# Sheet6.net
KiCad netlist of a schematic drawn in Altium Designer
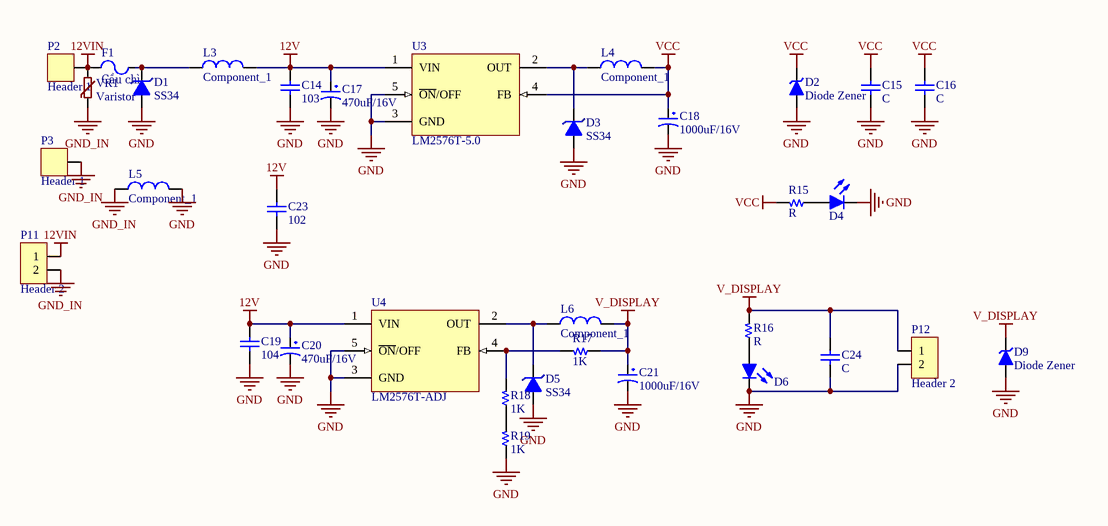
[diagram p0: Sheet6.SchDoc]

(export (version "E")
  (design (tool "Eeschema 10.0.6"))
  (components
    (comp (ref "C14")
      (value "103")
      (footprint "C 0805")
      (description "Capacitor non-pol")
      (libsource (lib "BKIT4U_LIB") (part "Capacitor NP"))
    )
    (comp (ref "C15")
      (value "C")
      (footprint "C 0805")
      (description "Capacitor non-pol")
      (libsource (lib "BKIT4U_LIB") (part "Capacitor NP"))
    )
    (comp (ref "C16")
      (value "C")
      (footprint "C 0805")
      (description "Capacitor non-pol")
      (libsource (lib "BKIT4U_LIB") (part "Capacitor NP"))
    )
    (comp (ref "C17")
      (value "470uF/16V")
      (footprint "WCAP-PSHP 8x8.7x3.1")
      (description "Cap 100uF/35V - 470uF/16V")
      (libsource (lib "syhaunguyen") (part "CP3"))
    )
    (comp (ref "C18")
      (value "1000uF/16V")
      (footprint "WCAP-PSHP 8x8.7x3.1")
      (description "Cap 1000uF/16V - 220uF/50V")
      (libsource (lib "syhaunguyen") (part "CP4"))
    )
    (comp (ref "C19")
      (value "104")
      (footprint "C 0805")
      (description "Capacitor non-pol")
      (libsource (lib "BKIT4U_LIB") (part "Capacitor NP"))
    )
    (comp (ref "C20")
      (value "470uF/16V")
      (footprint "WCAP-PSHP 8x8.7x3.1")
      (description "Cap 100uF/35V - 470uF/16V")
      (libsource (lib "syhaunguyen") (part "CP3"))
    )
    (comp (ref "C21")
      (value "1000uF/16V")
      (footprint "WCAP-PSHP 8x8.7x3.1")
      (description "Cap 1000uF/16V - 220uF/50V")
      (libsource (lib "syhaunguyen") (part "CP4"))
    )
    (comp (ref "C23")
      (value "102")
      (footprint "C 0805")
      (description "Capacitor non-pol")
      (libsource (lib "BKIT4U_LIB") (part "Capacitor NP"))
    )
    (comp (ref "C24")
      (value "C")
      (footprint "C 0805")
      (description "Capacitor non-pol")
      (libsource (lib "BKIT4U_LIB") (part "Capacitor NP"))
    )
    (comp (ref "D1")
      (value "SS34")
      (footprint "DO-214AC (SMA)")
      (libsource (lib "syhaunguyen") (part "Zener"))
    )
    (comp (ref "D2")
      (value "Diode Zener")
      (footprint "SOD-80")
      (description "Zener Diode")
      (fields (field (name "PUBLISHER") "Altium Limited"))
      (libsource (lib "BKIT4U_LIB") (part "Diode Zener"))
    )
    (comp (ref "D3")
      (value "SS34")
      (footprint "DO-214AC (SMA)")
      (libsource (lib "syhaunguyen") (part "Zener"))
    )
    (comp (ref "D4")
      (value "Led")
      (footprint "Led 0805 Blue")
      (description "Typical LED")
      (libsource (lib "chipfc_altium_libs") (part "Led"))
    )
    (comp (ref "D5")
      (value "SS34")
      (footprint "DO-214AC (SMA)")
      (libsource (lib "syhaunguyen") (part "Zener"))
    )
    (comp (ref "D6")
      (value "Led")
      (footprint "Led 0805 Blue")
      (description "Typical LED")
      (libsource (lib "chipfc_altium_libs") (part "Led"))
    )
    (comp (ref "D9")
      (value "Diode Zener")
      (footprint "SOD-80")
      (description "Zener Diode")
      (fields (field (name "PUBLISHER") "Altium Limited"))
      (libsource (lib "BKIT4U_LIB") (part "Diode Zener"))
    )
    (comp (ref "F1")
      (value "Cầu chì")
      (footprint "DCAR Fuse holder")
      (description "Fuse")
      (libsource (lib "chipfc_altium_libs") (part "Fuse"))
    )
    (comp (ref "L3")
      (value "Component_1")
      (footprint "1210")
      (libsource (lib "Integrated_Library1") (part "Component_1"))
    )
    (comp (ref "L4")
      (value "Component_1")
      (footprint "1210")
      (libsource (lib "Integrated_Library1") (part "Component_1"))
    )
    (comp (ref "L5")
      (value "Component_1")
      (footprint "1210")
      (libsource (lib "Integrated_Library1") (part "Component_1"))
    )
    (comp (ref "L6")
      (value "Component_1")
      (footprint "1210")
      (libsource (lib "Integrated_Library1") (part "Component_1"))
    )
    (comp (ref "P2")
      (value "Header 1")
      (footprint "HDR/Terminal/1/copper/8.8")
      (description "Header, 1-Pin")
      (libsource (lib "chipfc_altium_libs") (part "Header 1"))
    )
    (comp (ref "P3")
      (value "Header 1")
      (footprint "HDR/Terminal/1/copper/8.8")
      (description "Header, 1-Pin")
      (libsource (lib "chipfc_altium_libs") (part "Header 1"))
    )
    (comp (ref "P11")
      (value "Header 2")
      (footprint "HDR Domino 2")
      (description "Header, 2-Pin")
      (fields (field (name "PUBLISHER") "Altium Limited"))
      (libsource (lib "BKIT4U_LIB") (part "Header 2"))
    )
    (comp (ref "P12")
      (value "Header 2")
      (footprint "CON Header 2")
      (description "Header, 2-Pin")
      (fields (field (name "PUBLISHER") "Altium Limited"))
      (libsource (lib "") (part "Header 2_1"))
    )
    (comp (ref "R15")
      (value "R")
      (footprint "R 0805")
      (description "Resistor")
      (libsource (lib "chipfc_altium_libs") (part "Resistor"))
    )
    (comp (ref "R16")
      (value "R")
      (footprint "R 0805")
      (description "Resistor")
      (libsource (lib "chipfc_altium_libs") (part "Resistor"))
    )
    (comp (ref "R17")
      (value "1K")
      (footprint "R 0805")
      (description "Resistor")
      (libsource (lib "chipfc_altium_libs") (part "Resistor"))
    )
    (comp (ref "R18")
      (value "1K")
      (footprint "R 0805")
      (description "Resistor")
      (libsource (lib "chipfc_altium_libs") (part "Resistor"))
    )
    (comp (ref "R19")
      (value "1K")
      (footprint "R 0805")
      (description "Resistor")
      (libsource (lib "chipfc_altium_libs") (part "Resistor"))
    )
    (comp (ref "U3")
      (value "LM2576T-5.0")
      (footprint "D2-PACK5")
      (description "SIMPLE SWITCHER; 3A Step-Down Voltage Regulator")
      (fields
        (field (name "MANUFACTURER") "National Semiconductor")
        (field (name "DIGIKEYPARTNUMBER") "LM2576T-5.0-ND")
        (field (name "PUBLISHER") "Altium Limited")
      )
      (libsource (lib "General IC") (part "LM2576T-5.0"))
    )
    (comp (ref "U4")
      (value "LM2576T-ADJ")
      (footprint "D2-PACK5")
      (description "SIMPLE SWITCHER; 3A Step-Down Voltage Regulator")
      (fields
        (field (name "PARTNUMBER") "LM2576T-5.0")
        (field (name "MANUFACTURER") "National Semiconductor")
        (field (name "PUBLISHER") "Altium Limited")
      )
      (libsource (lib "General IC") (part "LM2576T-5.0"))
    )
    (comp (ref "VR1")
      (value "Varistor")
      (footprint "VARISTOR DISC 5MM/7MM")
      (libsource (lib "chipfc_altium_libs") (part "Varistor"))
    )
  )
  (nets
    (net (code "1") (name "12V") (class "Default")
      (node (ref "C14") (pin "1") (pinfunction "1_1") (pintype "passive"))
      (node (ref "C17") (pin "1") (pinfunction "1_1") (pintype "passive"))
      (node (ref "C19") (pin "1") (pinfunction "1_1") (pintype "passive"))
      (node (ref "C20") (pin "1") (pinfunction "1_1") (pintype "passive"))
      (node (ref "C23") (pin "1") (pinfunction "1_1") (pintype "passive"))
      (node (ref "L3") (pin "2") (pinfunction "2_2") (pintype "passive"))
      (node (ref "U3") (pin "1") (pinfunction "VIN_1") (pintype "power_in"))
      (node (ref "U4") (pin "1") (pinfunction "VIN_1") (pintype "power_in"))
    )
    (net (code "2") (name "12VIN") (class "Default")
      (node (ref "F1") (pin "1") (pinfunction "1_1") (pintype "passive"))
      (node (ref "P11") (pin "1") (pinfunction "1_1") (pintype "passive"))
      (node (ref "P2") (pin "1") (pinfunction "1_1") (pintype "passive"))
      (node (ref "VR1") (pin "1") (pinfunction "1_1") (pintype "passive"))
    )
    (net (code "3") (name "GND") (class "Default")
      (node (ref "C14") (pin "2") (pinfunction "2_2") (pintype "passive"))
      (node (ref "C15") (pin "2") (pinfunction "2_2") (pintype "passive"))
      (node (ref "C16") (pin "2") (pinfunction "2_2") (pintype "passive"))
      (node (ref "C17") (pin "2") (pinfunction "2_2") (pintype "passive"))
      (node (ref "C18") (pin "2") (pinfunction "2_2") (pintype "passive"))
      (node (ref "C19") (pin "2") (pinfunction "2_2") (pintype "passive"))
      (node (ref "C20") (pin "2") (pinfunction "2_2") (pintype "passive"))
      (node (ref "C21") (pin "2") (pinfunction "2_2") (pintype "passive"))
      (node (ref "C23") (pin "2") (pinfunction "2_2") (pintype "passive"))
      (node (ref "C24") (pin "2") (pinfunction "2_2") (pintype "passive"))
      (node (ref "D1") (pin "1") (pinfunction "A_1") (pintype "passive"))
      (node (ref "D2") (pin "1") (pinfunction "A_1") (pintype "passive"))
      (node (ref "D3") (pin "1") (pinfunction "A_1") (pintype "passive"))
      (node (ref "D4") (pin "2") (pinfunction "K_2") (pintype "passive"))
      (node (ref "D5") (pin "1") (pinfunction "A_1") (pintype "passive"))
      (node (ref "D6") (pin "2") (pinfunction "K_2") (pintype "passive"))
      (node (ref "D9") (pin "1") (pinfunction "A_1") (pintype "passive"))
      (node (ref "L5") (pin "2") (pinfunction "2_2") (pintype "passive"))
      (node (ref "P12") (pin "2") (pinfunction "2_2") (pintype "passive"))
      (node (ref "R19") (pin "1") (pinfunction "1_1") (pintype "passive"))
      (node (ref "U3") (pin "3") (pinfunction "GND_3") (pintype "power_in"))
      (node (ref "U3") (pin "5") (pinfunction "~{ON}/OFF_5") (pintype "input"))
      (node (ref "U4") (pin "3") (pinfunction "GND_3") (pintype "power_in"))
      (node (ref "U4") (pin "5") (pinfunction "~{ON}/OFF_5") (pintype "input"))
    )
    (net (code "4") (name "GND_IN") (class "Default")
      (node (ref "L5") (pin "1") (pinfunction "1_1") (pintype "passive"))
      (node (ref "P11") (pin "2") (pinfunction "2_2") (pintype "passive"))
      (node (ref "P3") (pin "1") (pinfunction "1_1") (pintype "passive"))
      (node (ref "VR1") (pin "2") (pinfunction "2_2") (pintype "passive"))
    )
    (net (code "5") (name "Net-(D1-K)") (class "Default")
      (node (ref "D1") (pin "2") (pinfunction "K_2") (pintype "passive"))
      (node (ref "F1") (pin "2") (pinfunction "2_2") (pintype "passive"))
      (node (ref "L3") (pin "1") (pinfunction "1_1") (pintype "passive"))
    )
    (net (code "6") (name "Net-(D3-K)") (class "Default")
      (node (ref "D3") (pin "2") (pinfunction "K_2") (pintype "passive"))
      (node (ref "L4") (pin "1") (pinfunction "1_1") (pintype "passive"))
      (node (ref "U3") (pin "2") (pinfunction "OUT_2") (pintype "power_in"))
    )
    (net (code "7") (name "Net-(D4-A)") (class "Default")
      (node (ref "D4") (pin "1") (pinfunction "A_1") (pintype "passive"))
      (node (ref "R15") (pin "1") (pinfunction "1_1") (pintype "passive"))
    )
    (net (code "8") (name "Net-(D5-K)") (class "Default")
      (node (ref "D5") (pin "2") (pinfunction "K_2") (pintype "passive"))
      (node (ref "L6") (pin "1") (pinfunction "1_1") (pintype "passive"))
      (node (ref "U4") (pin "2") (pinfunction "OUT_2") (pintype "power_in"))
    )
    (net (code "9") (name "Net-(D6-A)") (class "Default")
      (node (ref "D6") (pin "1") (pinfunction "A_1") (pintype "passive"))
      (node (ref "R16") (pin "1") (pinfunction "1_1") (pintype "passive"))
    )
    (net (code "10") (name "Net-(R18-Pad1)") (class "Default")
      (node (ref "R18") (pin "1") (pinfunction "1_1") (pintype "passive"))
      (node (ref "R19") (pin "2") (pinfunction "2_2") (pintype "passive"))
    )
    (net (code "11") (name "Net-(U4-FB)") (class "Default")
      (node (ref "R17") (pin "2") (pinfunction "2_2") (pintype "passive"))
      (node (ref "R18") (pin "2") (pinfunction "2_2") (pintype "passive"))
      (node (ref "U4") (pin "4") (pinfunction "FB_4") (pintype "input"))
    )
    (net (code "12") (name "VCC") (class "Default")
      (node (ref "C15") (pin "1") (pinfunction "1_1") (pintype "passive"))
      (node (ref "C16") (pin "1") (pinfunction "1_1") (pintype "passive"))
      (node (ref "C18") (pin "1") (pinfunction "1_1") (pintype "passive"))
      (node (ref "D2") (pin "2") (pinfunction "K_2") (pintype "passive"))
      (node (ref "L4") (pin "2") (pinfunction "2_2") (pintype "passive"))
      (node (ref "R15") (pin "2") (pinfunction "2_2") (pintype "passive"))
      (node (ref "U3") (pin "4") (pinfunction "FB_4") (pintype "input"))
    )
    (net (code "13") (name "V_DISPLAY") (class "Default")
      (node (ref "C21") (pin "1") (pinfunction "1_1") (pintype "passive"))
      (node (ref "C24") (pin "1") (pinfunction "1_1") (pintype "passive"))
      (node (ref "D9") (pin "2") (pinfunction "K_2") (pintype "passive"))
      (node (ref "L6") (pin "2") (pinfunction "2_2") (pintype "passive"))
      (node (ref "P12") (pin "1") (pinfunction "1_1") (pintype "passive"))
      (node (ref "R16") (pin "2") (pinfunction "2_2") (pintype "passive"))
      (node (ref "R17") (pin "1") (pinfunction "1_1") (pintype "passive"))
    )
  )
)
